# fmu.net
KiCad netlist of a schematic drawn in Altium Designer
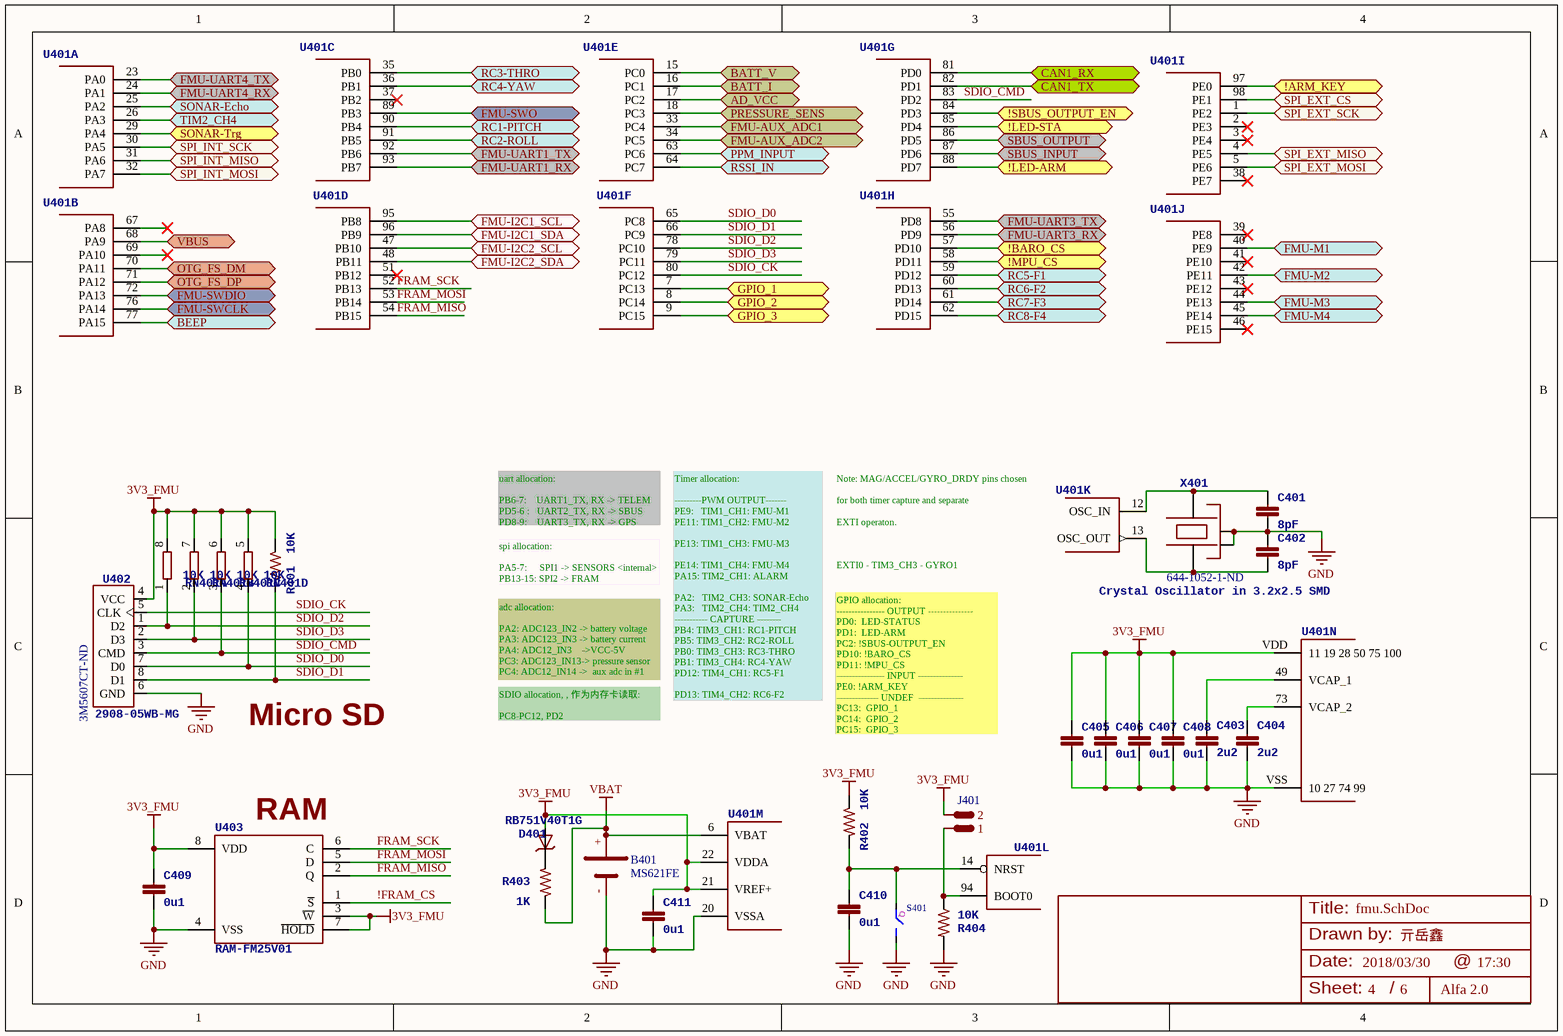
[diagram p0: fmu.SchDoc]

(export (version "E")
  (design (tool "Eeschema 10.0.6"))
  (components
    (comp (ref "B401")
      (value "MS621FE")
      (footprint "MS621FE")
      (description "MS Lithium Rechargeable Battery")
      (libsource (lib "Q's端子及图标") (part "BAT-MS621FE"))
    )
    (comp (ref "C401")
      (value "8pF")
      (footprint "0603-CAP")
      (description "CAP CER 8PF 50v c0g 0603")
      (libsource (lib "Q's无源元件类") (part "CAP0603-8pF"))
    )
    (comp (ref "C402")
      (value "8pF")
      (footprint "0603-CAP")
      (description "CAP CER 8PF 50v c0g 0603")
      (libsource (lib "Q's无源元件类") (part "CAP0603-8pF"))
    )
    (comp (ref "C403")
      (value "2u2")
      (footprint "0603-CAP")
      (description "Capacitor, 2.2uF, 16V, 10%, X6S, 0603, Ceramic")
      (fields (field (name "PARTNO") "C1608X6S1C225K080AC") (field (name "3DR_PARTNO") "ECM0619"))
      (libsource (lib "Q's无源元件类") (part "CAP0603-2.2uF"))
    )
    (comp (ref "C404")
      (value "2u2")
      (footprint "0603-CAP")
      (description "Capacitor, 2.2uF, 16V, 10%, X6S, 0603, Ceramic")
      (fields (field (name "PARTNO") "C1608X6S1C225K080AC") (field (name "3DR_PARTNO") "ECM0619"))
      (libsource (lib "Q's无源元件类") (part "CAP0603-2.2uF"))
    )
    (comp (ref "C405")
      (value "0u1")
      (footprint "0603-CAP")
      (description "Capacitor, 0.1uF, 16V, Y5V, 0402, Ceramic")
      (fields (field (name "PARTNO") "CC0402ZRY5V7BB104") (field (name "3DR_PARTNO") "ECM0700"))
      (libsource (lib "Q's无源元件类") (part "CAP0603-0.1uF"))
    )
    (comp (ref "C406")
      (value "0u1")
      (footprint "0603-CAP")
      (description "Capacitor, 0.1uF, 16V, Y5V, 0402, Ceramic")
      (fields (field (name "PARTNO") "CC0402ZRY5V7BB104") (field (name "3DR_PARTNO") "ECM0700"))
      (libsource (lib "Q's无源元件类") (part "CAP0603-0.1uF"))
    )
    (comp (ref "C407")
      (value "0u1")
      (footprint "0603-CAP")
      (description "Capacitor, 0.1uF, 16V, Y5V, 0402, Ceramic")
      (fields (field (name "PARTNO") "CC0402ZRY5V7BB104") (field (name "3DR_PARTNO") "ECM0700"))
      (libsource (lib "Q's无源元件类") (part "CAP0603-0.1uF"))
    )
    (comp (ref "C408")
      (value "0u1")
      (footprint "0603-CAP")
      (description "Capacitor, 0.1uF, 16V, Y5V, 0402, Ceramic")
      (fields (field (name "PARTNO") "CC0402ZRY5V7BB104") (field (name "3DR_PARTNO") "ECM0700"))
      (libsource (lib "Q's无源元件类") (part "CAP0603-0.1uF"))
    )
    (comp (ref "C409")
      (value "0u1")
      (footprint "0603-CAP")
      (description "Capacitor, 0.1uF, 16V, Y5V, 0402, Ceramic")
      (fields (field (name "PARTNO") "CC0402ZRY5V7BB104") (field (name "3DR_PARTNO") "ECM0700"))
      (libsource (lib "Q's无源元件类") (part "CAP0603-0.1uF"))
    )
    (comp (ref "C410")
      (value "0u1")
      (footprint "0603-CAP")
      (description "Capacitor, 0.1uF, 16V, Y5V, 0402, Ceramic")
      (fields (field (name "PARTNO") "CC0402ZRY5V7BB104") (field (name "3DR_PARTNO") "ECM0700"))
      (libsource (lib "Q's无源元件类") (part "CAP0603-0.1uF"))
    )
    (comp (ref "C411")
      (value "0u1")
      (footprint "0603-CAP")
      (description "Capacitor, 0.1uF, 16V, Y5V, 0402, Ceramic")
      (fields (field (name "PARTNO") "CC0402ZRY5V7BB104") (field (name "3DR_PARTNO") "ECM0700"))
      (libsource (lib "Q's无源元件类") (part "CAP0603-0.1uF"))
    )
    (comp (ref "D401")
      (value "RB751V40T1G")
      (footprint "SOD-323")
      (description "DIODE SCHOTTKY 40V 30mA , 0.34V, SOD323")
      (libsource (lib "Q's无源元件类") (part "DIODE-SBD_SOD323"))
    )
    (comp (ref "J401")
      (value "HDR 2X1")
      (footprint "HDR2X1")
      (description "排针, 2X1 pins")
      (libsource (lib "Q's端子及图标") (part "HDR 2X1"))
    )
    (comp (ref "R401")
      (value "10K")
      (footprint "0603-RES")
      (description "RES 10K OHM 1/10W 5% 0603")
      (libsource (lib "Q's无源元件类") (part "RES0603-10K"))
    )
    (comp (ref "R402")
      (value "10K")
      (footprint "0603-RES")
      (description "RES 10K OHM 1/10W 5% 0603")
      (libsource (lib "Q's无源元件类") (part "RES0603-10K"))
    )
    (comp (ref "R403")
      (value "1K")
      (footprint "0603-RES")
      (description "RES 1K OHM 1/10W 5% 0603")
      (libsource (lib "Q's无源元件类") (part "RES0603-1K"))
    )
    (comp (ref "R404")
      (value "10K")
      (footprint "0603-RES")
      (description "RES 10K OHM 1/10W 5% 0603")
      (libsource (lib "Q's无源元件类") (part "RES0603-10K"))
    )
    (comp (ref "RN401")
      (value "10K")
      (footprint "0603*4")
      (description "RES ARRAY 10K OHM 4 RES 0603")
      (libsource (lib "Q's无源元件类") (part "RES4P-0603-10K"))
    )
    (comp (ref "S401")
      (value "轻触开关 贴片3*6*2.5mm")
      (footprint "SMD-SWITCH-2P")
      (description "按键 3*6*2.5mm 轻触开关 贴片2脚 白色")
      (libsource (lib "Q's无源元件类") (part "SWITCH-1"))
    )
    (comp (ref "U401")
      (value "STM32F427VI qfp 100 pin")
      (footprint "LQFP100")
      (description "REV 3 Silicon or later IC MCU ARM 2MB FLASH 100LQFP")
      (fields (field (name "3DR_PARTNO") "ECM0841"))
      (libsource (lib "Q's控制芯片类") (part "STM32F4X7VX"))
    )
    (comp (ref "U402")
      (value "2908-05WB-MG")
      (footprint "MICROSD")
      (description "CONN MICRO SD CARD PUSH-PUSH R/A")
      (fields (field (name "3DR_PARTNO") "ECM0485") (field (name "SUPPLIER PART NUMBER 1") "3M5607CT-ND"))
      (libsource (lib "Q's端子及图标") (part "MICROSD-SDI"))
    )
    (comp (ref "U403")
      (value "RAM-FM25V01")
      (footprint "SO08")
      (description "IC FRAM 128KBIT 40MHZ 8SOIC")
      (fields (field (name "PARTNO") "FM25V01-G") (field (name "3DR_PARTNO") "ECM0826"))
      (libsource (lib "Q's有源芯片类") (part "RAM-FM25V01"))
    )
    (comp (ref "X401")
      (value "Crystal Oscillator in 3.2x2.5 SMD")
      (footprint "3225-OSC")
      (description "CRYSTAL 24MHZ 8PF SMD")
      (fields
        (field (name "3DR_PARTNO") "ECM0708")
        (field (name "PARTNO") "NX3225SA-24.000MHZ-STD-CSR-1")
        (field (name "SUPPLIER PART NUMBER 1") "644-1052-1-ND")
      )
      (libsource (lib "Q's无源元件类") (part "OSCILLATOR-3225"))
    )
  )
  (nets
    (net (code "1") (name "/!ARM_KEY") (class "Default")
      (node (ref "U401") (pin "97") (pinfunction "PE0_97") (pintype "passive"))
    )
    (net (code "2") (name "/!BARO_CS") (class "Default")
      (node (ref "U401") (pin "57") (pinfunction "PD10_57") (pintype "passive"))
    )
    (net (code "3") (name "/!FRAM_CS") (class "Default")
      (node (ref "U403") (pin "1") (pinfunction "~{S}_1") (pintype "passive"))
    )
    (net (code "4") (name "/!LED-ARM") (class "Default")
      (node (ref "U401") (pin "88") (pinfunction "PD7_88") (pintype "passive"))
    )
    (net (code "5") (name "/!LED-STA") (class "Default")
      (node (ref "U401") (pin "85") (pinfunction "PD4_85") (pintype "passive"))
    )
    (net (code "6") (name "/!MPU_CS") (class "Default")
      (node (ref "U401") (pin "58") (pinfunction "PD11_58") (pintype "passive"))
    )
    (net (code "7") (name "/!SBUS_OUTPUT_EN") (class "Default")
      (node (ref "U401") (pin "84") (pinfunction "PD3_84") (pintype "passive"))
    )
    (net (code "8") (name "/AD_VCC") (class "Default")
      (node (ref "U401") (pin "17") (pinfunction "PC2_17") (pintype "passive"))
    )
    (net (code "9") (name "/BATT_I") (class "Default")
      (node (ref "U401") (pin "16") (pinfunction "PC1_16") (pintype "passive"))
    )
    (net (code "10") (name "/BATT_V") (class "Default")
      (node (ref "U401") (pin "15") (pinfunction "PC0_15") (pintype "passive"))
    )
    (net (code "11") (name "/BEEP") (class "Default")
      (node (ref "U401") (pin "77") (pinfunction "PA15_77") (pintype "passive"))
    )
    (net (code "12") (name "/CAN1_RX") (class "Default")
      (node (ref "U401") (pin "81") (pinfunction "PD0_81") (pintype "passive"))
    )
    (net (code "13") (name "/CAN1_TX") (class "Default")
      (node (ref "U401") (pin "82") (pinfunction "PD1_82") (pintype "passive"))
    )
    (net (code "14") (name "/FMU-AUX_ADC1") (class "Default")
      (node (ref "U401") (pin "33") (pinfunction "PC4_33") (pintype "passive"))
    )
    (net (code "15") (name "/FMU-AUX_ADC2") (class "Default")
      (node (ref "U401") (pin "34") (pinfunction "PC5_34") (pintype "passive"))
    )
    (net (code "16") (name "/FMU-I2C1_SCL") (class "Default")
      (node (ref "U401") (pin "95") (pinfunction "PB8_95") (pintype "passive"))
    )
    (net (code "17") (name "/FMU-I2C1_SDA") (class "Default")
      (node (ref "U401") (pin "96") (pinfunction "PB9_96") (pintype "passive"))
    )
    (net (code "18") (name "/FMU-I2C2_SCL") (class "Default")
      (node (ref "U401") (pin "47") (pinfunction "PB10_47") (pintype "passive"))
    )
    (net (code "19") (name "/FMU-I2C2_SDA") (class "Default")
      (node (ref "U401") (pin "48") (pinfunction "PB11_48") (pintype "passive"))
    )
    (net (code "20") (name "/FMU-M1") (class "Default")
      (node (ref "U401") (pin "40") (pinfunction "PE9_40") (pintype "passive"))
    )
    (net (code "21") (name "/FMU-M2") (class "Default")
      (node (ref "U401") (pin "42") (pinfunction "PE11_42") (pintype "passive"))
    )
    (net (code "22") (name "/FMU-M3") (class "Default")
      (node (ref "U401") (pin "44") (pinfunction "PE13_44") (pintype "passive"))
    )
    (net (code "23") (name "/FMU-M4") (class "Default")
      (node (ref "U401") (pin "45") (pinfunction "PE14_45") (pintype "passive"))
    )
    (net (code "24") (name "/FMU-SWCLK") (class "Default")
      (node (ref "U401") (pin "76") (pinfunction "PA14_76") (pintype "passive"))
    )
    (net (code "25") (name "/FMU-SWDIO") (class "Default")
      (node (ref "U401") (pin "72") (pinfunction "PA13_72") (pintype "passive"))
    )
    (net (code "26") (name "/FMU-SWO") (class "Default")
      (node (ref "U401") (pin "89") (pinfunction "PB3_89") (pintype "passive"))
    )
    (net (code "27") (name "/FMU-UART1_RX") (class "Default")
      (node (ref "U401") (pin "93") (pinfunction "PB7_93") (pintype "passive"))
    )
    (net (code "28") (name "/FMU-UART1_TX") (class "Default")
      (node (ref "U401") (pin "92") (pinfunction "PB6_92") (pintype "passive"))
    )
    (net (code "29") (name "/FMU-UART3_RX") (class "Default")
      (node (ref "U401") (pin "56") (pinfunction "PD9_56") (pintype "passive"))
    )
    (net (code "30") (name "/FMU-UART3_TX") (class "Default")
      (node (ref "U401") (pin "55") (pinfunction "PD8_55") (pintype "passive"))
    )
    (net (code "31") (name "/FMU-UART4_RX") (class "Default")
      (node (ref "U401") (pin "24") (pinfunction "PA1_24") (pintype "passive"))
    )
    (net (code "32") (name "/FMU-UART4_TX") (class "Default")
      (node (ref "U401") (pin "23") (pinfunction "PA0_23") (pintype "passive"))
    )
    (net (code "33") (name "/FRAM_MISO") (class "Default")
      (node (ref "U401") (pin "54") (pinfunction "PB15_54") (pintype "passive"))
      (node (ref "U403") (pin "2") (pinfunction "Q_2") (pintype "passive"))
    )
    (net (code "34") (name "/FRAM_MOSI") (class "Default")
      (node (ref "U401") (pin "53") (pinfunction "PB14_53") (pintype "passive"))
      (node (ref "U403") (pin "5") (pinfunction "D_5") (pintype "passive"))
    )
    (net (code "35") (name "/FRAM_SCK") (class "Default")
      (node (ref "U401") (pin "52") (pinfunction "PB13_52") (pintype "passive"))
      (node (ref "U403") (pin "6") (pinfunction "C_6") (pintype "passive"))
    )
    (net (code "36") (name "/GPIO_1") (class "Default")
      (node (ref "U401") (pin "7") (pinfunction "PC13_7") (pintype "passive"))
    )
    (net (code "37") (name "/GPIO_2") (class "Default")
      (node (ref "U401") (pin "8") (pinfunction "PC14_8") (pintype "passive"))
    )
    (net (code "38") (name "/GPIO_3") (class "Default")
      (node (ref "U401") (pin "9") (pinfunction "PC15_9") (pintype "passive"))
    )
    (net (code "39") (name "/OTG_FS_DM") (class "Default")
      (node (ref "U401") (pin "70") (pinfunction "PA11_70") (pintype "passive"))
    )
    (net (code "40") (name "/OTG_FS_DP") (class "Default")
      (node (ref "U401") (pin "71") (pinfunction "PA12_71") (pintype "passive"))
    )
    (net (code "41") (name "/PPM_INPUT") (class "Default")
      (node (ref "U401") (pin "63") (pinfunction "PC6_63") (pintype "passive"))
    )
    (net (code "42") (name "/PRESSURE_SENS") (class "Default")
      (node (ref "U401") (pin "18") (pinfunction "PC3_18") (pintype "passive"))
    )
    (net (code "43") (name "/RC1-PITCH") (class "Default")
      (node (ref "U401") (pin "90") (pinfunction "PB4_90") (pintype "passive"))
    )
    (net (code "44") (name "/RC2-ROLL") (class "Default")
      (node (ref "U401") (pin "91") (pinfunction "PB5_91") (pintype "passive"))
    )
    (net (code "45") (name "/RC3-THRO") (class "Default")
      (node (ref "U401") (pin "35") (pinfunction "PB0_35") (pintype "passive"))
    )
    (net (code "46") (name "/RC4-YAW") (class "Default")
      (node (ref "U401") (pin "36") (pinfunction "PB1_36") (pintype "passive"))
    )
    (net (code "47") (name "/RC5-F1") (class "Default")
      (node (ref "U401") (pin "59") (pinfunction "PD12_59") (pintype "passive"))
    )
    (net (code "48") (name "/RC6-F2") (class "Default")
      (node (ref "U401") (pin "60") (pinfunction "PD13_60") (pintype "passive"))
    )
    (net (code "49") (name "/RC7-F3") (class "Default")
      (node (ref "U401") (pin "61") (pinfunction "PD14_61") (pintype "passive"))
    )
    (net (code "50") (name "/RC8-F4") (class "Default")
      (node (ref "U401") (pin "62") (pinfunction "PD15_62") (pintype "passive"))
    )
    (net (code "51") (name "/RSSI_IN") (class "Default")
      (node (ref "U401") (pin "64") (pinfunction "PC7_64") (pintype "passive"))
    )
    (net (code "52") (name "/SBUS_INPUT") (class "Default")
      (node (ref "U401") (pin "87") (pinfunction "PD6_87") (pintype "passive"))
    )
    (net (code "53") (name "/SBUS_OUTPUT") (class "Default")
      (node (ref "U401") (pin "86") (pinfunction "PD5_86") (pintype "passive"))
    )
    (net (code "54") (name "/SDIO_CK") (class "Default")
      (node (ref "U401") (pin "80") (pinfunction "PC12_80") (pintype "passive"))
      (node (ref "U402") (pin "5") (pinfunction "CLK_5") (pintype "passive"))
    )
    (net (code "55") (name "/SDIO_CMD") (class "Default")
      (node (ref "RN401") (pin "3") (pinfunction "1_3") (pintype "passive"))
      (node (ref "U401") (pin "83") (pinfunction "PD2_83") (pintype "passive"))
      (node (ref "U402") (pin "3") (pinfunction "CMD_3") (pintype "passive"))
    )
    (net (code "56") (name "/SDIO_D0") (class "Default")
      (node (ref "RN401") (pin "4") (pinfunction "1_4") (pintype "passive"))
      (node (ref "U401") (pin "65") (pinfunction "PC8_65") (pintype "passive"))
      (node (ref "U402") (pin "7") (pinfunction "D0_7") (pintype "passive"))
    )
    (net (code "57") (name "/SDIO_D1") (class "Default")
      (node (ref "R401") (pin "2") (pinfunction "2_2") (pintype "passive"))
      (node (ref "U401") (pin "66") (pinfunction "PC9_66") (pintype "passive"))
      (node (ref "U402") (pin "8") (pinfunction "D1_8") (pintype "passive"))
    )
    (net (code "58") (name "/SDIO_D2") (class "Default")
      (node (ref "RN401") (pin "1") (pinfunction "1_1") (pintype "passive"))
      (node (ref "U401") (pin "78") (pinfunction "PC10_78") (pintype "passive"))
      (node (ref "U402") (pin "1") (pinfunction "D2_1") (pintype "passive"))
    )
    (net (code "59") (name "/SDIO_D3") (class "Default")
      (node (ref "RN401") (pin "2") (pinfunction "1_2") (pintype "passive"))
      (node (ref "U401") (pin "79") (pinfunction "PC11_79") (pintype "passive"))
      (node (ref "U402") (pin "2") (pinfunction "D3_2") (pintype "passive"))
    )
    (net (code "60") (name "/SONAR-Echo") (class "Default")
      (node (ref "U401") (pin "25") (pinfunction "PA2_25") (pintype "passive"))
    )
    (net (code "61") (name "/SONAR-Trg") (class "Default")
      (node (ref "U401") (pin "29") (pinfunction "PA4_29") (pintype "passive"))
    )
    (net (code "62") (name "/SPI_EXT_CS") (class "Default")
      (node (ref "U401") (pin "98") (pinfunction "PE1_98") (pintype "passive"))
    )
    (net (code "63") (name "/SPI_EXT_MISO") (class "Default")
      (node (ref "U401") (pin "4") (pinfunction "PE5_4") (pintype "passive"))
    )
    (net (code "64") (name "/SPI_EXT_MOSI") (class "Default")
      (node (ref "U401") (pin "5") (pinfunction "PE6_5") (pintype "passive"))
    )
    (net (code "65") (name "/SPI_EXT_SCK") (class "Default")
      (node (ref "U401") (pin "1") (pinfunction "PE2_1") (pintype "passive"))
    )
    (net (code "66") (name "/SPI_INT_MISO") (class "Default")
      (node (ref "U401") (pin "31") (pinfunction "PA6_31") (pintype "passive"))
    )
    (net (code "67") (name "/SPI_INT_MOSI") (class "Default")
      (node (ref "U401") (pin "32") (pinfunction "PA7_32") (pintype "passive"))
    )
    (net (code "68") (name "/SPI_INT_SCK") (class "Default")
      (node (ref "U401") (pin "30") (pinfunction "PA5_30") (pintype "passive"))
    )
    (net (code "69") (name "/TIM2_CH4") (class "Default")
      (node (ref "U401") (pin "26") (pinfunction "PA3_26") (pintype "passive"))
    )
    (net (code "70") (name "/VBUS") (class "Default")
      (node (ref "U401") (pin "68") (pinfunction "PA9_68") (pintype "passive"))
    )
    (net (code "71") (name "3V3_FMU") (class "Default")
      (node (ref "C405") (pin "P$1") (pinfunction "1_P$1") (pintype "passive"))
      (node (ref "C406") (pin "P$1") (pinfunction "1_P$1") (pintype "passive"))
      (node (ref "C407") (pin "P$1") (pinfunction "1_P$1") (pintype "passive"))
      (node (ref "C408") (pin "P$1") (pinfunction "1_P$1") (pintype "passive"))
      (node (ref "C409") (pin "P$1") (pinfunction "1_P$1") (pintype "passive"))
      (node (ref "C411") (pin "P$1") (pinfunction "1_P$1") (pintype "passive"))
      (node (ref "D401") (pin "A") (pinfunction "A_A") (pintype "passive"))
      (node (ref "J401") (pin "2") (pinfunction "2_2") (pintype "passive"))
      (node (ref "R401") (pin "1") (pinfunction "1_1") (pintype "passive"))
      (node (ref "R402") (pin "1") (pinfunction "1_1") (pintype "passive"))
      (node (ref "RN401") (pin "5") (pinfunction "2_5") (pintype "passive"))
      (node (ref "RN401") (pin "6") (pinfunction "2_6") (pintype "passive"))
      (node (ref "RN401") (pin "7") (pinfunction "2_7") (pintype "passive"))
      (node (ref "RN401") (pin "8") (pinfunction "2_8") (pintype "passive"))
      (node (ref "U401") (pin "21") (pinfunction "VREF+_21") (pintype "passive"))
      (node (ref "U401") (pin "22") (pinfunction "VDDA_22") (pintype "power_in"))
      (node (ref "U401") (pin "VDD") (pinfunction "11_19_28_50_75_100_VDD") (pintype "power_in"))
      (node (ref "U402") (pin "4") (pinfunction "VCC_4") (pintype "passive"))
      (node (ref "U403") (pin "3") (pinfunction "~{W}_3") (pintype "passive"))
      (node (ref "U403") (pin "7") (pinfunction "~{HOLD}_7") (pintype "passive"))
      (node (ref "U403") (pin "8") (pinfunction "VDD_8") (pintype "passive"))
    )
    (net (code "72") (name "GND") (class "Default")
      (node (ref "B401") (pin "-") (pinfunction "-_-") (pintype "passive"))
      (node (ref "C401") (pin "P$2") (pinfunction "2_P$2") (pintype "passive"))
      (node (ref "C402") (pin "P$1") (pinfunction "1_P$1") (pintype "passive"))
      (node (ref "C403") (pin "P$2") (pinfunction "2_P$2") (pintype "passive"))
      (node (ref "C404") (pin "P$2") (pinfunction "2_P$2") (pintype "passive"))
      (node (ref "C405") (pin "P$2") (pinfunction "2_P$2") (pintype "passive"))
      (node (ref "C406") (pin "P$2") (pinfunction "2_P$2") (pintype "passive"))
      (node (ref "C407") (pin "P$2") (pinfunction "2_P$2") (pintype "passive"))
      (node (ref "C408") (pin "P$2") (pinfunction "2_P$2") (pintype "passive"))
      (node (ref "C409") (pin "P$2") (pinfunction "2_P$2") (pintype "passive"))
      (node (ref "C410") (pin "P$2") (pinfunction "2_P$2") (pintype "passive"))
      (node (ref "C411") (pin "P$2") (pinfunction "2_P$2") (pintype "passive"))
      (node (ref "R404") (pin "2") (pinfunction "2_2") (pintype "passive"))
      (node (ref "S401") (pin "2") (pinfunction "2_2") (pintype "passive"))
      (node (ref "U401") (pin "20") (pinfunction "VSSA_20") (pintype "power_in"))
      (node (ref "U401") (pin "VSS") (pinfunction "10_27_74_99_VSS") (pintype "power_in"))
      (node (ref "U402") (pin "6") (pinfunction "GND_6") (pintype "passive"))
      (node (ref "U403") (pin "4") (pinfunction "VSS_4") (pintype "passive"))
      (node (ref "X401") (pin "2") (pinfunction "NC_2_2") (pintype "passive"))
      (node (ref "X401") (pin "4") (pinfunction "NC_4_4") (pintype "passive"))
    )
    (net (code "73") (name "Net-(C401-1)") (class "Default")
      (node (ref "C401") (pin "P$1") (pinfunction "1_P$1") (pintype "passive"))
      (node (ref "U401") (pin "12") (pinfunction "OSC_IN_12") (pintype "passive"))
      (node (ref "X401") (pin "3") (pinfunction "3_3") (pintype "passive"))
    )
    (net (code "74") (name "Net-(C402-2)") (class "Default")
      (node (ref "C402") (pin "P$2") (pinfunction "2_P$2") (pintype "passive"))
      (node (ref "U401") (pin "13") (pinfunction "OSC_OUT_13") (pintype "output"))
      (node (ref "X401") (pin "1") (pinfunction "1_1") (pintype "passive"))
    )
    (net (code "75") (name "Net-(C403-1)") (class "Default")
      (node (ref "C403") (pin "P$1") (pinfunction "1_P$1") (pintype "passive"))
      (node (ref "U401") (pin "49") (pinfunction "VCAP_1_49") (pintype "power_in"))
    )
    (net (code "76") (name "Net-(C404-1)") (class "Default")
      (node (ref "C404") (pin "P$1") (pinfunction "1_P$1") (pintype "passive"))
      (node (ref "U401") (pin "73") (pinfunction "VCAP_2_73") (pintype "power_in"))
    )
    (net (code "77") (name "Net-(C410-1)") (class "Default")
      (node (ref "C410") (pin "P$1") (pinfunction "1_P$1") (pintype "passive"))
      (node (ref "R402") (pin "2") (pinfunction "2_2") (pintype "passive"))
      (node (ref "S401") (pin "1") (pinfunction "1_1") (pintype "passive"))
      (node (ref "U401") (pin "14") (pinfunction "NRST_14") (pintype "passive"))
    )
    (net (code "78") (name "Net-(D401-PadC)") (class "Default")
      (node (ref "D401") (pin "C") (pinfunction "C_C") (pintype "passive"))
      (node (ref "R403") (pin "2") (pinfunction "2_2") (pintype "passive"))
    )
    (net (code "79") (name "Net-(U401L-BOOT0)") (class "Default")
      (node (ref "J401") (pin "1") (pinfunction "1_1") (pintype "passive"))
      (node (ref "R404") (pin "1") (pinfunction "1_1") (pintype "passive"))
      (node (ref "U401") (pin "94") (pinfunction "BOOT0_94") (pintype "passive"))
    )
    (net (code "80") (name "VBAT") (class "Default")
      (node (ref "B401") (pin "+") (pinfunction "+_+") (pintype "passive"))
      (node (ref "R403") (pin "1") (pinfunction "1_1") (pintype "passive"))
      (node (ref "U401") (pin "6") (pinfunction "VBAT_6") (pintype "power_in"))
    )
    (net (code "81") (name "unconnected-(U401B-PA8-Pad67)") (class "Default")
      (node (ref "U401") (pin "67") (pinfunction "PA8_67") (pintype "passive+no_connect"))
    )
    (net (code "82") (name "unconnected-(U401B-PA10-Pad69)") (class "Default")
      (node (ref "U401") (pin "69") (pinfunction "PA10_69") (pintype "passive+no_connect"))
    )
    (net (code "83") (name "unconnected-(U401C-PB2-Pad37)") (class "Default")
      (node (ref "U401") (pin "37") (pinfunction "PB2_37") (pintype "passive+no_connect"))
    )
    (net (code "84") (name "unconnected-(U401D-PB12-Pad51)") (class "Default")
      (node (ref "U401") (pin "51") (pinfunction "PB12_51") (pintype "passive+no_connect"))
    )
    (net (code "85") (name "unconnected-(U401I-PE3-Pad2)") (class "Default")
      (node (ref "U401") (pin "2") (pinfunction "PE3_2") (pintype "passive+no_connect"))
    )
    (net (code "86") (name "unconnected-(U401I-PE4-Pad3)") (class "Default")
      (node (ref "U401") (pin "3") (pinfunction "PE4_3") (pintype "passive+no_connect"))
    )
    (net (code "87") (name "unconnected-(U401I-PE7-Pad38)") (class "Default")
      (node (ref "U401") (pin "38") (pinfunction "PE7_38") (pintype "passive+no_connect"))
    )
    (net (code "88") (name "unconnected-(U401J-PE8-Pad39)") (class "Default")
      (node (ref "U401") (pin "39") (pinfunction "PE8_39") (pintype "passive+no_connect"))
    )
    (net (code "89") (name "unconnected-(U401J-PE10-Pad41)") (class "Default")
      (node (ref "U401") (pin "41") (pinfunction "PE10_41") (pintype "passive+no_connect"))
    )
    (net (code "90") (name "unconnected-(U401J-PE12-Pad43)") (class "Default")
      (node (ref "U401") (pin "43") (pinfunction "PE12_43") (pintype "passive+no_connect"))
    )
    (net (code "91") (name "unconnected-(U401J-PE15-Pad46)") (class "Default")
      (node (ref "U401") (pin "46") (pinfunction "PE15_46") (pintype "passive+no_connect"))
    )
  )
)
